# tsmp-resistors.net
KiCad netlist of a schematic drawn in Altium Designer
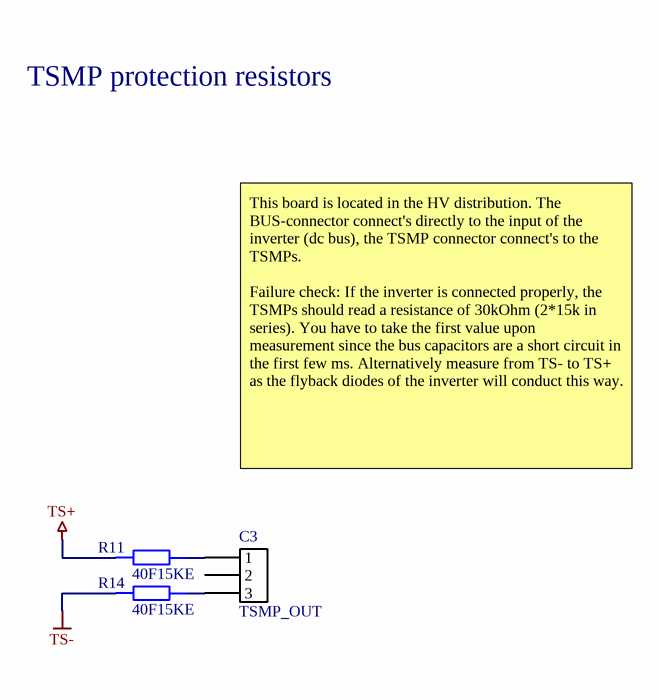
[diagram p0: tsmp-resistors.SchDoc]

(export (version "E")
  (design (tool "Eeschema 10.0.6"))
  (components
    (comp (ref "C3")
      (value "TSMP_OUT")
      (footprint "43650-0309")
      (description "Molex Micro-Fit 3.0 3-Pin\r\n600V\r\n8.5A")
      (libsource (lib "Standardbauteile") (part "MicroFit3.0 3-Pin"))
    )
    (comp (ref "R11")
      (value "40F15KE")
      (footprint "OHMITE_40_SERIES")
      (description "Wirewound Resistors 10watt 15K 1% Axial")
      (fields (field (name "MANUFACTURER") "Ohmite") (field (name "TOLERANCE") "1%"))
      (libsource (lib "Leon") (part "40F15KE"))
    )
    (comp (ref "R14")
      (value "40F15KE")
      (footprint "OHMITE_40_SERIES")
      (description "Wirewound Resistors 10watt 15K 1% Axial")
      (fields (field (name "MANUFACTURER") "Ohmite") (field (name "TOLERANCE") "1%"))
      (libsource (lib "Leon") (part "40F15KE"))
    )
  )
  (nets
    (net (code "1") (name "Net-(C3-Pad1)") (class "Default")
      (node (ref "C3") (pin "1") (pinfunction "1_1") (pintype "passive"))
      (node (ref "R11") (pin "2") (pinfunction "2_2") (pintype "passive"))
    )
    (net (code "2") (name "Net-(C3-Pad3)") (class "Default")
      (node (ref "C3") (pin "3") (pinfunction "3_3") (pintype "passive"))
      (node (ref "R14") (pin "2") (pinfunction "2_2") (pintype "passive"))
    )
    (net (code "3") (name "TS+") (class "Default")
      (node (ref "R11") (pin "1") (pinfunction "1_1") (pintype "passive"))
    )
    (net (code "4") (name "TS-") (class "Default")
      (node (ref "R14") (pin "1") (pinfunction "1_1") (pintype "passive"))
    )
    (net (code "5") (name "unconnected-(C3-Pad2)") (class "Default")
      (node (ref "C3") (pin "2") (pinfunction "2_2") (pintype "passive"))
    )
  )
)
